# juanK.net
KiCad netlist of a schematic drawn in EAGLE
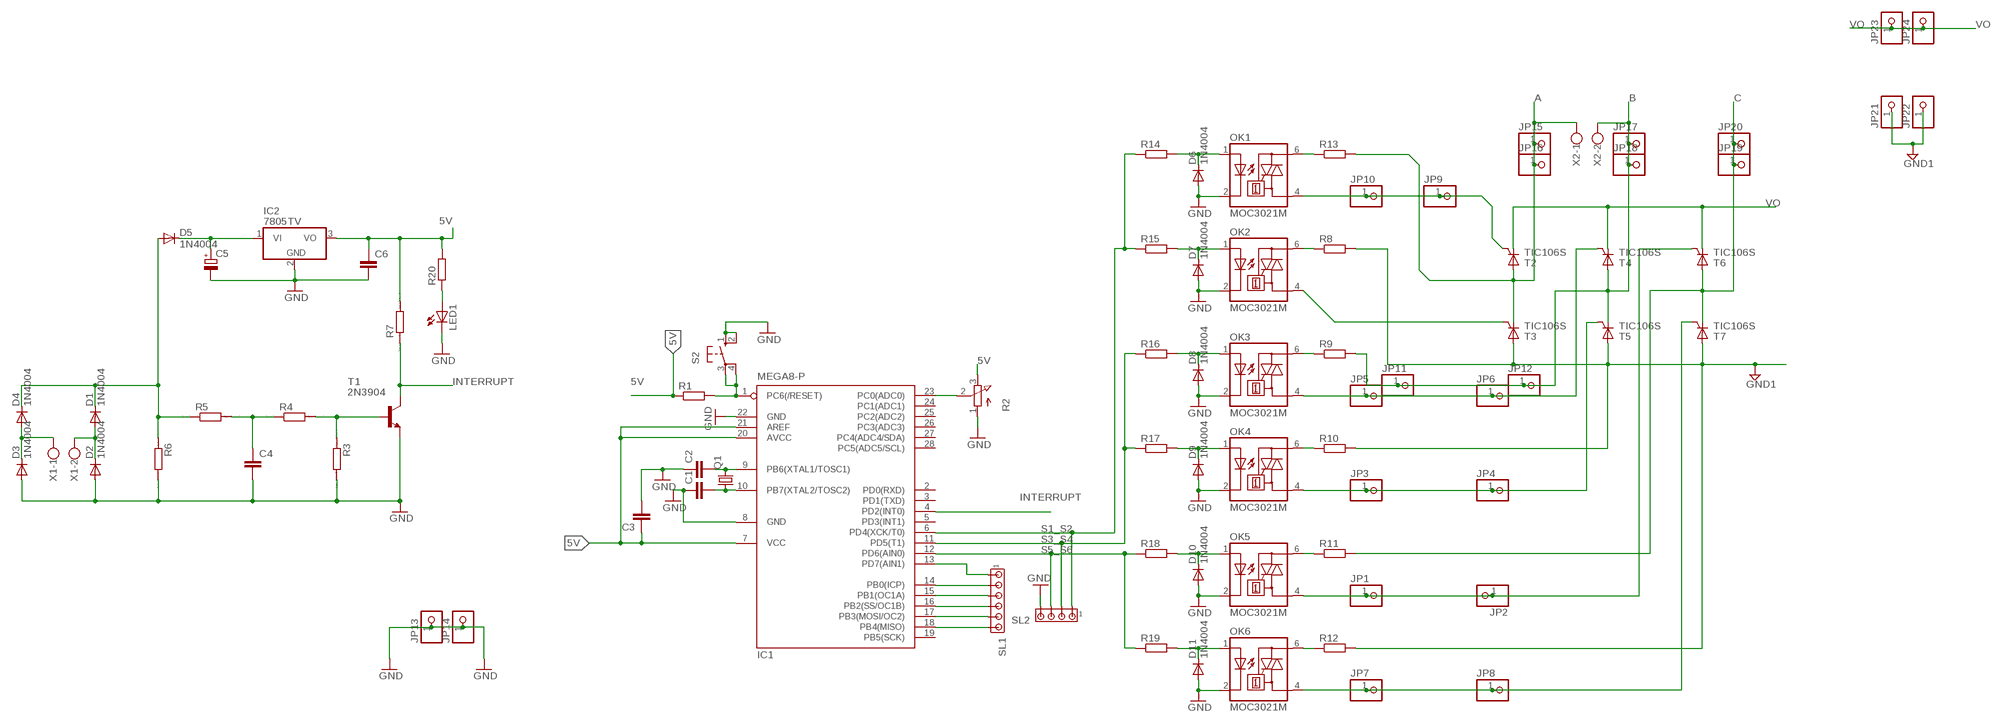
[diagram p0: schematic, sheet 1]

(export (version "E")
  (design (tool "Eeschema 10.0.6"))
  (components
    (comp (ref "C1")
      (value "C2,5-3")
      (footprint "eagle-import:C2.5-3")
      (libsource (lib "eagle-import") (part "C2,5-3"))
    )
    (comp (ref "C2")
      (value "C2,5-3")
      (footprint "eagle-import:C2.5-3")
      (libsource (lib "eagle-import") (part "C2,5-3"))
    )
    (comp (ref "C3")
      (value "C2,5-3")
      (footprint "eagle-import:C2.5-3")
      (libsource (lib "eagle-import") (part "C2,5-3"))
    )
    (comp (ref "C4")
      (value "C-EU025-025X050")
      (footprint "eagle-import:C025-025X050")
      (libsource (lib "eagle-import") (part "C-EU025-025X050"))
    )
    (comp (ref "C5")
      (value "CPOL-EUE5-10.5")
      (footprint "eagle-import:E5-10,5")
      (libsource (lib "eagle-import") (part "CPOL-EUE5-10.5"))
    )
    (comp (ref "C6")
      (value "C-EU025-025X050")
      (footprint "eagle-import:C025-025X050")
      (libsource (lib "eagle-import") (part "C-EU025-025X050"))
    )
    (comp (ref "D1")
      (value "1N4004")
      (footprint "eagle-import:DO41-10")
      (libsource (lib "eagle-import") (part "1N4004"))
    )
    (comp (ref "D2")
      (value "1N4004")
      (footprint "eagle-import:DO41-10")
      (libsource (lib "eagle-import") (part "1N4004"))
    )
    (comp (ref "D3")
      (value "1N4004")
      (footprint "eagle-import:DO41-10")
      (libsource (lib "eagle-import") (part "1N4004"))
    )
    (comp (ref "D4")
      (value "1N4004")
      (footprint "eagle-import:DO41-10")
      (libsource (lib "eagle-import") (part "1N4004"))
    )
    (comp (ref "D5")
      (value "1N4004")
      (footprint "eagle-import:DO41-10")
      (libsource (lib "eagle-import") (part "1N4004"))
    )
    (comp (ref "D6")
      (value "1N4004")
      (footprint "eagle-import:DO41-10")
      (libsource (lib "eagle-import") (part "1N4004"))
    )
    (comp (ref "D7")
      (value "1N4004")
      (footprint "eagle-import:DO41-10")
      (libsource (lib "eagle-import") (part "1N4004"))
    )
    (comp (ref "D8")
      (value "1N4004")
      (footprint "eagle-import:DO41-10")
      (libsource (lib "eagle-import") (part "1N4004"))
    )
    (comp (ref "D9")
      (value "1N4004")
      (footprint "eagle-import:DO41-10")
      (libsource (lib "eagle-import") (part "1N4004"))
    )
    (comp (ref "D10")
      (value "1N4004")
      (footprint "eagle-import:DO41-10")
      (libsource (lib "eagle-import") (part "1N4004"))
    )
    (comp (ref "D11")
      (value "1N4004")
      (footprint "eagle-import:DO41-10")
      (libsource (lib "eagle-import") (part "1N4004"))
    )
    (comp (ref "IC1")
      (value "MEGA8-P")
      (footprint "eagle-import:DIL28-3")
      (libsource (lib "eagle-import") (part "MEGA8-P"))
    )
    (comp (ref "IC2")
      (value "7805TV")
      (footprint "eagle-import:TO220V")
      (libsource (lib "eagle-import") (part "78TV05"))
    )
    (comp (ref "JP1")
      (value "PINHD-1X1")
      (footprint "eagle-import:1X01")
      (libsource (lib "eagle-import") (part "PINHD-1X1"))
    )
    (comp (ref "JP2")
      (value "PINHD-1X1")
      (footprint "eagle-import:1X01")
      (libsource (lib "eagle-import") (part "PINHD-1X1"))
    )
    (comp (ref "JP3")
      (value "PINHD-1X1")
      (footprint "eagle-import:1X01")
      (libsource (lib "eagle-import") (part "PINHD-1X1"))
    )
    (comp (ref "JP4")
      (value "PINHD-1X1")
      (footprint "eagle-import:1X01")
      (libsource (lib "eagle-import") (part "PINHD-1X1"))
    )
    (comp (ref "JP5")
      (value "PINHD-1X1")
      (footprint "eagle-import:1X01")
      (libsource (lib "eagle-import") (part "PINHD-1X1"))
    )
    (comp (ref "JP6")
      (value "PINHD-1X1")
      (footprint "eagle-import:1X01")
      (libsource (lib "eagle-import") (part "PINHD-1X1"))
    )
    (comp (ref "JP7")
      (value "PINHD-1X1")
      (footprint "eagle-import:1X01")
      (libsource (lib "eagle-import") (part "PINHD-1X1"))
    )
    (comp (ref "JP8")
      (value "PINHD-1X1")
      (footprint "eagle-import:1X01")
      (libsource (lib "eagle-import") (part "PINHD-1X1"))
    )
    (comp (ref "JP9")
      (value "PINHD-1X1")
      (footprint "eagle-import:1X01")
      (libsource (lib "eagle-import") (part "PINHD-1X1"))
    )
    (comp (ref "JP10")
      (value "PINHD-1X1")
      (footprint "eagle-import:1X01")
      (libsource (lib "eagle-import") (part "PINHD-1X1"))
    )
    (comp (ref "JP11")
      (value "PINHD-1X1")
      (footprint "eagle-import:1X01")
      (libsource (lib "eagle-import") (part "PINHD-1X1"))
    )
    (comp (ref "JP12")
      (value "PINHD-1X1")
      (footprint "eagle-import:1X01")
      (libsource (lib "eagle-import") (part "PINHD-1X1"))
    )
    (comp (ref "JP13")
      (value "PINHD-1X1")
      (footprint "eagle-import:1X01")
      (libsource (lib "eagle-import") (part "PINHD-1X1"))
    )
    (comp (ref "JP14")
      (value "PINHD-1X1")
      (footprint "eagle-import:1X01")
      (libsource (lib "eagle-import") (part "PINHD-1X1"))
    )
    (comp (ref "JP15")
      (value "PINHD-1X1")
      (footprint "eagle-import:1X01")
      (libsource (lib "eagle-import") (part "PINHD-1X1"))
    )
    (comp (ref "JP16")
      (value "PINHD-1X1")
      (footprint "eagle-import:1X01")
      (libsource (lib "eagle-import") (part "PINHD-1X1"))
    )
    (comp (ref "JP17")
      (value "PINHD-1X1")
      (footprint "eagle-import:1X01")
      (libsource (lib "eagle-import") (part "PINHD-1X1"))
    )
    (comp (ref "JP18")
      (value "PINHD-1X1")
      (footprint "eagle-import:1X01")
      (libsource (lib "eagle-import") (part "PINHD-1X1"))
    )
    (comp (ref "JP19")
      (value "PINHD-1X1")
      (footprint "eagle-import:1X01")
      (libsource (lib "eagle-import") (part "PINHD-1X1"))
    )
    (comp (ref "JP20")
      (value "PINHD-1X1")
      (footprint "eagle-import:1X01")
      (libsource (lib "eagle-import") (part "PINHD-1X1"))
    )
    (comp (ref "JP21")
      (value "PINHD-1X1")
      (footprint "eagle-import:1X01")
      (libsource (lib "eagle-import") (part "PINHD-1X1"))
    )
    (comp (ref "JP22")
      (value "PINHD-1X1")
      (footprint "eagle-import:1X01")
      (libsource (lib "eagle-import") (part "PINHD-1X1"))
    )
    (comp (ref "JP23")
      (value "PINHD-1X1")
      (footprint "eagle-import:1X01")
      (libsource (lib "eagle-import") (part "PINHD-1X1"))
    )
    (comp (ref "JP24")
      (value "PINHD-1X1")
      (footprint "eagle-import:1X01")
      (libsource (lib "eagle-import") (part "PINHD-1X1"))
    )
    (comp (ref "LED1")
      (value "LED3MM")
      (footprint "eagle-import:LED3MM")
      (libsource (lib "eagle-import") (part "LED3MM"))
    )
    (comp (ref "OK1")
      (value "MOC3021M")
      (footprint "eagle-import:DIL06")
      (fields (field (name "MF") "FAIRCHILD SEMICONDUCTOR") (field (name "MPN") "MOC3021-M"))
      (libsource (lib "eagle-import") (part "MOC30M21"))
    )
    (comp (ref "OK2")
      (value "MOC3021M")
      (footprint "eagle-import:DIL06")
      (fields (field (name "MF") "FAIRCHILD SEMICONDUCTOR") (field (name "MPN") "MOC3021-M"))
      (libsource (lib "eagle-import") (part "MOC30M21"))
    )
    (comp (ref "OK3")
      (value "MOC3021M")
      (footprint "eagle-import:DIL06")
      (fields (field (name "MF") "FAIRCHILD SEMICONDUCTOR") (field (name "MPN") "MOC3021-M"))
      (libsource (lib "eagle-import") (part "MOC30M21"))
    )
    (comp (ref "OK4")
      (value "MOC3021M")
      (footprint "eagle-import:DIL06")
      (fields (field (name "MF") "FAIRCHILD SEMICONDUCTOR") (field (name "MPN") "MOC3021-M"))
      (libsource (lib "eagle-import") (part "MOC30M21"))
    )
    (comp (ref "OK5")
      (value "MOC3021M")
      (footprint "eagle-import:DIL06")
      (fields (field (name "MF") "FAIRCHILD SEMICONDUCTOR") (field (name "MPN") "MOC3021-M"))
      (libsource (lib "eagle-import") (part "MOC30M21"))
    )
    (comp (ref "OK6")
      (value "MOC3021M")
      (footprint "eagle-import:DIL06")
      (fields (field (name "MF") "FAIRCHILD SEMICONDUCTOR") (field (name "MPN") "MOC3021-M"))
      (libsource (lib "eagle-import") (part "MOC30M21"))
    )
    (comp (ref "Q1")
      (value "CRYSTALHC49U70")
      (footprint "eagle-import:HC49U70")
      (libsource (lib "eagle-import") (part "CRYSTALHC49U70"))
    )
    (comp (ref "R1")
      (value "R-EU_0204/5")
      (footprint "eagle-import:0204_5")
      (libsource (lib "eagle-import") (part "R-EU_0204/5"))
    )
    (comp (ref "R2")
      (value "3RP/1610N")
      (footprint "eagle-import:3RP_1610N")
      (libsource (lib "eagle-import") (part "3RP/1610N"))
    )
    (comp (ref "R3")
      (value "R0204/7")
      (footprint "eagle-import:0204_7")
      (libsource (lib "eagle-import") (part "R0204/7"))
    )
    (comp (ref "R4")
      (value "R0204/7")
      (footprint "eagle-import:0204_7")
      (libsource (lib "eagle-import") (part "R0204/7"))
    )
    (comp (ref "R5")
      (value "R0204/7")
      (footprint "eagle-import:0204_7")
      (libsource (lib "eagle-import") (part "R0204/7"))
    )
    (comp (ref "R6")
      (value "R0204/7")
      (footprint "eagle-import:0204_7")
      (libsource (lib "eagle-import") (part "R0204/7"))
    )
    (comp (ref "R7")
      (value "R0204/7")
      (footprint "eagle-import:0204_7")
      (libsource (lib "eagle-import") (part "R0204/7"))
    )
    (comp (ref "R8")
      (value "R-EU_0817/22")
      (footprint "eagle-import:P0817_22")
      (libsource (lib "eagle-import") (part "resistor_R-EU_0817/22"))
    )
    (comp (ref "R9")
      (value "R-EU_0817/22")
      (footprint "eagle-import:P0817_22")
      (libsource (lib "eagle-import") (part "resistor_R-EU_0817/22"))
    )
    (comp (ref "R10")
      (value "R-EU_0817/22")
      (footprint "eagle-import:P0817_22")
      (libsource (lib "eagle-import") (part "resistor_R-EU_0817/22"))
    )
    (comp (ref "R11")
      (value "R-EU_0817/22")
      (footprint "eagle-import:P0817_22")
      (libsource (lib "eagle-import") (part "resistor_R-EU_0817/22"))
    )
    (comp (ref "R12")
      (value "R-EU_0817/22")
      (footprint "eagle-import:P0817_22")
      (libsource (lib "eagle-import") (part "resistor_R-EU_0817/22"))
    )
    (comp (ref "R13")
      (value "R-EU_0817/22")
      (footprint "eagle-import:P0817_22")
      (libsource (lib "eagle-import") (part "resistor_R-EU_0817/22"))
    )
    (comp (ref "R14")
      (value "R-EU_0204/7")
      (footprint "eagle-import:0204_7")
      (libsource (lib "eagle-import") (part "resistor_R-EU_0204/7"))
    )
    (comp (ref "R15")
      (value "R-EU_0204/7")
      (footprint "eagle-import:0204_7")
      (libsource (lib "eagle-import") (part "resistor_R-EU_0204/7"))
    )
    (comp (ref "R16")
      (value "R-EU_0204/7")
      (footprint "eagle-import:0204_7")
      (libsource (lib "eagle-import") (part "resistor_R-EU_0204/7"))
    )
    (comp (ref "R17")
      (value "R-EU_0204/7")
      (footprint "eagle-import:0204_7")
      (libsource (lib "eagle-import") (part "resistor_R-EU_0204/7"))
    )
    (comp (ref "R18")
      (value "R-EU_0204/7")
      (footprint "eagle-import:0204_7")
      (libsource (lib "eagle-import") (part "resistor_R-EU_0204/7"))
    )
    (comp (ref "R19")
      (value "R-EU_0204/7")
      (footprint "eagle-import:0204_7")
      (libsource (lib "eagle-import") (part "resistor_R-EU_0204/7"))
    )
    (comp (ref "R20")
      (value "R-EU_0204/5")
      (footprint "eagle-import:0204_5")
      (libsource (lib "eagle-import") (part "R-EU_0204/5"))
    )
    (comp (ref "S2")
      (value "10-XX")
      (footprint "eagle-import:B3F-10XX")
      (fields (field (name "MPN") "B3F-1000"))
      (libsource (lib "eagle-import") (part "10-XX"))
    )
    (comp (ref "SL1")
      (value "MTA06-100")
      (footprint "eagle-import:10X06MTA")
      (libsource (lib "eagle-import") (part "MTA06-100"))
    )
    (comp (ref "SL2")
      (value "MTA04-100")
      (footprint "eagle-import:10X04MTA")
      (libsource (lib "eagle-import") (part "MTA04-100"))
    )
    (comp (ref "T1")
      (value "2N3904")
      (footprint "eagle-import:TO92")
      (libsource (lib "eagle-import") (part "2N3904"))
    )
    (comp (ref "T2")
      (value "TIC106S")
      (footprint "eagle-import:TIC106S")
      (libsource (lib "eagle-import") (part "TIC106S"))
    )
    (comp (ref "T3")
      (value "TIC106S")
      (footprint "eagle-import:TIC106S")
      (libsource (lib "eagle-import") (part "TIC106S"))
    )
    (comp (ref "T4")
      (value "TIC106S")
      (footprint "eagle-import:TIC106S")
      (libsource (lib "eagle-import") (part "TIC106S"))
    )
    (comp (ref "T5")
      (value "TIC106S")
      (footprint "eagle-import:TIC106S")
      (libsource (lib "eagle-import") (part "TIC106S"))
    )
    (comp (ref "T6")
      (value "TIC106S")
      (footprint "eagle-import:TIC106S")
      (libsource (lib "eagle-import") (part "TIC106S"))
    )
    (comp (ref "T7")
      (value "TIC106S")
      (footprint "eagle-import:TIC106S")
      (libsource (lib "eagle-import") (part "TIC106S"))
    )
    (comp (ref "X1")
      (value "W237-102")
      (footprint "eagle-import:W237-102")
      (fields (field (name "MPN") "237-102"))
      (libsource (lib "eagle-import") (part "W237-102"))
    )
    (comp (ref "X2")
      (value "W237-102")
      (footprint "eagle-import:W237-102")
      (fields (field (name "MPN") "237-102"))
      (libsource (lib "eagle-import") (part "W237-102"))
    )
  )
  (nets
    (net (code "1") (name "/A") (class "Default")
      (node (ref "JP15") (pin "1") (pinfunction "1_1") (pintype "passive"))
      (node (ref "JP16") (pin "1") (pinfunction "1_1") (pintype "passive"))
      (node (ref "R13") (pin "2") (pinfunction "2_2") (pintype "passive"))
      (node (ref "T2") (pin "A") (pinfunction "A_A") (pintype "passive"))
      (node (ref "T3") (pin "C") (pinfunction "C_C") (pintype "passive"))
      (node (ref "X2") (pin "1") (pinfunction "KL_1") (pintype "passive"))
    )
    (net (code "2") (name "/B") (class "Default")
      (node (ref "JP11") (pin "1") (pinfunction "1_1") (pintype "passive"))
      (node (ref "JP12") (pin "1") (pinfunction "1_1") (pintype "passive"))
      (node (ref "JP17") (pin "1") (pinfunction "1_1") (pintype "passive"))
      (node (ref "JP18") (pin "1") (pinfunction "1_1") (pintype "passive"))
      (node (ref "R9") (pin "2") (pinfunction "2_2") (pintype "passive"))
      (node (ref "T4") (pin "A") (pinfunction "A_A") (pintype "passive"))
      (node (ref "T5") (pin "C") (pinfunction "C_C") (pintype "passive"))
      (node (ref "X2") (pin "2") (pinfunction "KL_2") (pintype "passive"))
    )
    (net (code "3") (name "/C") (class "Default")
      (node (ref "JP19") (pin "1") (pinfunction "1_1") (pintype "passive"))
      (node (ref "JP20") (pin "1") (pinfunction "1_1") (pintype "passive"))
      (node (ref "R11") (pin "2") (pinfunction "2_2") (pintype "passive"))
      (node (ref "T6") (pin "A") (pinfunction "A_A") (pintype "passive"))
      (node (ref "T7") (pin "C") (pinfunction "C_C") (pintype "passive"))
    )
    (net (code "4") (name "/INTERRUPT") (class "Default")
      (node (ref "IC1") (pin "4") (pinfunction "PD2(INT0)_4") (pintype "bidirectional"))
      (node (ref "R7") (pin "1") (pinfunction "1_1") (pintype "passive"))
      (node (ref "T1") (pin "1") (pinfunction "C_1") (pintype "passive"))
    )
    (net (code "5") (name "/S1_S2") (class "Default")
      (node (ref "IC1") (pin "6") (pinfunction "PD4(XCK/T0)_6") (pintype "bidirectional"))
      (node (ref "R14") (pin "1") (pinfunction "1_1") (pintype "passive"))
      (node (ref "R15") (pin "1") (pinfunction "1_1") (pintype "passive"))
      (node (ref "SL2") (pin "1") (pinfunction "1_1") (pintype "passive"))
    )
    (net (code "6") (name "/S3_S4") (class "Default")
      (node (ref "IC1") (pin "11") (pinfunction "PD5(T1)_11") (pintype "bidirectional"))
      (node (ref "R16") (pin "1") (pinfunction "1_1") (pintype "passive"))
      (node (ref "R17") (pin "1") (pinfunction "1_1") (pintype "passive"))
      (node (ref "SL2") (pin "2") (pinfunction "2_2") (pintype "passive"))
    )
    (net (code "7") (name "/S5_S6") (class "Default")
      (node (ref "IC1") (pin "12") (pinfunction "PD6(AIN0)_12") (pintype "bidirectional"))
      (node (ref "R18") (pin "1") (pinfunction "1_1") (pintype "passive"))
      (node (ref "R19") (pin "1") (pinfunction "1_1") (pintype "passive"))
      (node (ref "SL2") (pin "3") (pinfunction "3_3") (pintype "passive"))
    )
    (net (code "8") (name "/VO") (class "Default")
      (node (ref "JP23") (pin "1") (pinfunction "1_1") (pintype "passive"))
      (node (ref "JP24") (pin "1") (pinfunction "1_1") (pintype "passive"))
      (node (ref "T2") (pin "C") (pinfunction "C_C") (pintype "passive"))
      (node (ref "T4") (pin "C") (pinfunction "C_C") (pintype "passive"))
      (node (ref "T6") (pin "C") (pinfunction "C_C") (pintype "passive"))
    )
    (net (code "9") (name "5V") (class "Default")
      (node (ref "C3") (pin "1") (pinfunction "1_1") (pintype "passive"))
      (node (ref "C6") (pin "1") (pinfunction "1_1") (pintype "passive"))
      (node (ref "IC1") (pin "20") (pinfunction "AVCC_20") (pintype "power_in"))
      (node (ref "IC1") (pin "21") (pinfunction "AREF_21") (pintype "passive"))
      (node (ref "IC1") (pin "7") (pinfunction "VCC_7") (pintype "power_in"))
      (node (ref "IC2") (pin "3") (pinfunction "VO_3") (pintype "passive"))
      (node (ref "R1") (pin "1") (pinfunction "1_1") (pintype "passive"))
      (node (ref "R2") (pin "3") (pinfunction "E_3") (pintype "passive"))
      (node (ref "R20") (pin "2") (pinfunction "2_2") (pintype "passive"))
      (node (ref "R7") (pin "2") (pinfunction "2_2") (pintype "passive"))
    )
    (net (code "10") (name "GND") (class "Default")
      (node (ref "C1") (pin "1") (pinfunction "1_1") (pintype "passive"))
      (node (ref "C2") (pin "1") (pinfunction "1_1") (pintype "passive"))
      (node (ref "C3") (pin "2") (pinfunction "2_2") (pintype "passive"))
      (node (ref "C4") (pin "2") (pinfunction "2_2") (pintype "passive"))
      (node (ref "C5") (pin "-") (pinfunction "-_-") (pintype "passive"))
      (node (ref "C6") (pin "2") (pinfunction "2_2") (pintype "passive"))
      (node (ref "D10") (pin "A") (pinfunction "A_A") (pintype "passive"))
      (node (ref "D11") (pin "A") (pinfunction "A_A") (pintype "passive"))
      (node (ref "D2") (pin "A") (pinfunction "A_A") (pintype "passive"))
      (node (ref "D3") (pin "A") (pinfunction "A_A") (pintype "passive"))
      (node (ref "D6") (pin "A") (pinfunction "A_A") (pintype "passive"))
      (node (ref "D7") (pin "A") (pinfunction "A_A") (pintype "passive"))
      (node (ref "D8") (pin "A") (pinfunction "A_A") (pintype "passive"))
      (node (ref "D9") (pin "A") (pinfunction "A_A") (pintype "passive"))
      (node (ref "IC1") (pin "22") (pinfunction "GND_22") (pintype "power_in"))
      (node (ref "IC1") (pin "8") (pinfunction "GND_8") (pintype "power_in"))
      (node (ref "IC2") (pin "2") (pinfunction "GND_2") (pintype "passive"))
      (node (ref "JP13") (pin "1") (pinfunction "1_1") (pintype "passive"))
      (node (ref "JP14") (pin "1") (pinfunction "1_1") (pintype "passive"))
      (node (ref "LED1") (pin "K") (pinfunction "C_K") (pintype "passive"))
      (node (ref "OK1") (pin "2") (pinfunction "C_2") (pintype "passive"))
      (node (ref "OK2") (pin "2") (pinfunction "C_2") (pintype "passive"))
      (node (ref "OK3") (pin "2") (pinfunction "C_2") (pintype "passive"))
      (node (ref "OK4") (pin "2") (pinfunction "C_2") (pintype "passive"))
      (node (ref "OK5") (pin "2") (pinfunction "C_2") (pintype "passive"))
      (node (ref "OK6") (pin "2") (pinfunction "C_2") (pintype "passive"))
      (node (ref "R2") (pin "1") (pinfunction "A_1") (pintype "passive"))
      (node (ref "R3") (pin "2") (pinfunction "2_2") (pintype "passive"))
      (node (ref "R6") (pin "2") (pinfunction "2_2") (pintype "passive"))
      (node (ref "S2") (pin "1") (pinfunction "S_1") (pintype "passive"))
      (node (ref "S2") (pin "2") (pinfunction "S1_2") (pintype "passive"))
      (node (ref "SL2") (pin "4") (pinfunction "4_4") (pintype "passive"))
      (node (ref "T1") (pin "3") (pinfunction "E_3") (pintype "passive"))
    )
    (net (code "11") (name "GND1") (class "Default")
      (node (ref "JP21") (pin "1") (pinfunction "1_1") (pintype "passive"))
      (node (ref "JP22") (pin "1") (pinfunction "1_1") (pintype "passive"))
      (node (ref "R10") (pin "2") (pinfunction "2_2") (pintype "passive"))
      (node (ref "R12") (pin "2") (pinfunction "2_2") (pintype "passive"))
      (node (ref "R8") (pin "2") (pinfunction "2_2") (pintype "passive"))
      (node (ref "T3") (pin "A") (pinfunction "A_A") (pintype "passive"))
      (node (ref "T5") (pin "A") (pinfunction "A_A") (pintype "passive"))
      (node (ref "T7") (pin "A") (pinfunction "A_A") (pintype "passive"))
    )
    (net (code "12") (name "Net-(C4-Pad1)") (class "Default")
      (node (ref "C4") (pin "1") (pinfunction "1_1") (pintype "passive"))
      (node (ref "R4") (pin "1") (pinfunction "1_1") (pintype "passive"))
      (node (ref "R5") (pin "2") (pinfunction "2_2") (pintype "passive"))
    )
    (net (code "13") (name "Net-(D1-PadC)") (class "Default")
      (node (ref "D1") (pin "C") (pinfunction "C_C") (pintype "passive"))
      (node (ref "D4") (pin "C") (pinfunction "C_C") (pintype "passive"))
      (node (ref "D5") (pin "A") (pinfunction "A_A") (pintype "passive"))
      (node (ref "R5") (pin "1") (pinfunction "1_1") (pintype "passive"))
      (node (ref "R6") (pin "1") (pinfunction "1_1") (pintype "passive"))
    )
    (net (code "14") (name "Net-(IC1-PB0(ICP))") (class "Default")
      (node (ref "IC1") (pin "14") (pinfunction "PB0(ICP)_14") (pintype "bidirectional"))
      (node (ref "SL1") (pin "2") (pinfunction "2_2") (pintype "passive"))
    )
    (net (code "15") (name "Net-(IC1-PB1(OC1A))") (class "Default")
      (node (ref "IC1") (pin "15") (pinfunction "PB1(OC1A)_15") (pintype "bidirectional"))
      (node (ref "SL1") (pin "3") (pinfunction "3_3") (pintype "passive"))
    )
    (net (code "16") (name "Net-(IC1-PB2(SS{slash}OC1B))") (class "Default")
      (node (ref "IC1") (pin "16") (pinfunction "PB2(SS/OC1B)_16") (pintype "bidirectional"))
      (node (ref "SL1") (pin "4") (pinfunction "4_4") (pintype "passive"))
    )
    (net (code "17") (name "Net-(IC1-PB3(MOSI{slash}OC2))") (class "Default")
      (node (ref "IC1") (pin "17") (pinfunction "PB3(MOSI/OC2)_17") (pintype "bidirectional"))
      (node (ref "SL1") (pin "5") (pinfunction "5_5") (pintype "passive"))
    )
    (net (code "18") (name "Net-(IC1-PB4(MISO))") (class "Default")
      (node (ref "IC1") (pin "18") (pinfunction "PB4(MISO)_18") (pintype "bidirectional"))
      (node (ref "SL1") (pin "6") (pinfunction "6_6") (pintype "passive"))
    )
    (net (code "19") (name "Net-(IC1-PB6(XTAL1{slash}TOSC1))") (class "Default")
      (node (ref "C2") (pin "2") (pinfunction "2_2") (pintype "passive"))
      (node (ref "IC1") (pin "9") (pinfunction "PB6(XTAL1/TOSC1)_9") (pintype "bidirectional"))
      (node (ref "Q1") (pin "2") (pinfunction "2_2") (pintype "passive"))
    )
    (net (code "20") (name "Net-(IC1-PB7(XTAL2{slash}TOSC2))") (class "Default")
      (node (ref "C1") (pin "2") (pinfunction "2_2") (pintype "passive"))
      (node (ref "IC1") (pin "10") (pinfunction "PB7(XTAL2/TOSC2)_10") (pintype "bidirectional"))
      (node (ref "Q1") (pin "1") (pinfunction "1_1") (pintype "passive"))
    )
    (net (code "21") (name "Net-(IC1-PC0(ADC0))") (class "Default")
      (node (ref "IC1") (pin "23") (pinfunction "PC0(ADC0)_23") (pintype "bidirectional"))
      (node (ref "R2") (pin "2") (pinfunction "S_2") (pintype "passive"))
    )
    (net (code "22") (name "Net-(IC1-PC6({slash}RESET))") (class "Default")
      (node (ref "IC1") (pin "1") (pinfunction "PC6(/RESET)_1") (pintype "bidirectional"))
      (node (ref "R1") (pin "2") (pinfunction "2_2") (pintype "passive"))
      (node (ref "S2") (pin "3") (pinfunction "P_3") (pintype "passive"))
      (node (ref "S2") (pin "4") (pinfunction "P1_4") (pintype "passive"))
    )
    (net (code "23") (name "Net-(IC1-PD7(AIN1))") (class "Default")
      (node (ref "IC1") (pin "13") (pinfunction "PD7(AIN1)_13") (pintype "bidirectional"))
      (node (ref "SL1") (pin "1") (pinfunction "1_1") (pintype "passive"))
    )
    (net (code "24") (name "Net-(IC2-VI)") (class "Default")
      (node (ref "C5") (pin "+") (pinfunction "+_+") (pintype "passive"))
      (node (ref "D5") (pin "C") (pinfunction "C_C") (pintype "passive"))
      (node (ref "IC2") (pin "1") (pinfunction "VI_1") (pintype "input"))
    )
    (net (code "25") (name "Net-(LED1-PadA)") (class "Default")
      (node (ref "LED1") (pin "A") (pinfunction "A_A") (pintype "passive"))
      (node (ref "R20") (pin "1") (pinfunction "1_1") (pintype "passive"))
    )
    (net (code "26") (name "Net-(OK1-A)") (class "Default")
      (node (ref "D6") (pin "C") (pinfunction "C_C") (pintype "passive"))
      (node (ref "OK1") (pin "1") (pinfunction "A_1") (pintype "passive"))
      (node (ref "R14") (pin "2") (pinfunction "2_2") (pintype "passive"))
    )
    (net (code "27") (name "Net-(OK1-A1)") (class "Default")
      (node (ref "JP10") (pin "1") (pinfunction "1_1") (pintype "passive"))
      (node (ref "JP9") (pin "1") (pinfunction "1_1") (pintype "passive"))
      (node (ref "OK1") (pin "4") (pinfunction "A1_4") (pintype "passive"))
      (node (ref "T2") (pin "G") (pinfunction "G_G") (pintype "passive"))
    )
    (net (code "28") (name "Net-(OK1-A2)") (class "Default")
      (node (ref "OK1") (pin "6") (pinfunction "A2_6") (pintype "passive"))
      (node (ref "R13") (pin "1") (pinfunction "1_1") (pintype "passive"))
    )
    (net (code "29") (name "Net-(OK2-A)") (class "Default")
      (node (ref "D7") (pin "C") (pinfunction "C_C") (pintype "passive"))
      (node (ref "OK2") (pin "1") (pinfunction "A_1") (pintype "passive"))
      (node (ref "R15") (pin "2") (pinfunction "2_2") (pintype "passive"))
    )
    (net (code "30") (name "Net-(OK2-A1)") (class "Default")
      (node (ref "OK2") (pin "4") (pinfunction "A1_4") (pintype "passive"))
      (node (ref "T3") (pin "G") (pinfunction "G_G") (pintype "passive"))
    )
    (net (code "31") (name "Net-(OK2-A2)") (class "Default")
      (node (ref "OK2") (pin "6") (pinfunction "A2_6") (pintype "passive"))
      (node (ref "R8") (pin "1") (pinfunction "1_1") (pintype "passive"))
    )
    (net (code "32") (name "Net-(OK3-A)") (class "Default")
      (node (ref "D8") (pin "C") (pinfunction "C_C") (pintype "passive"))
      (node (ref "OK3") (pin "1") (pinfunction "A_1") (pintype "passive"))
      (node (ref "R16") (pin "2") (pinfunction "2_2") (pintype "passive"))
    )
    (net (code "33") (name "Net-(OK3-A1)") (class "Default")
      (node (ref "JP5") (pin "1") (pinfunction "1_1") (pintype "passive"))
      (node (ref "JP6") (pin "1") (pinfunction "1_1") (pintype "passive"))
      (node (ref "OK3") (pin "4") (pinfunction "A1_4") (pintype "passive"))
      (node (ref "T4") (pin "G") (pinfunction "G_G") (pintype "passive"))
    )
    (net (code "34") (name "Net-(OK3-A2)") (class "Default")
      (node (ref "OK3") (pin "6") (pinfunction "A2_6") (pintype "passive"))
      (node (ref "R9") (pin "1") (pinfunction "1_1") (pintype "passive"))
    )
    (net (code "35") (name "Net-(OK4-A)") (class "Default")
      (node (ref "D9") (pin "C") (pinfunction "C_C") (pintype "passive"))
      (node (ref "OK4") (pin "1") (pinfunction "A_1") (pintype "passive"))
      (node (ref "R17") (pin "2") (pinfunction "2_2") (pintype "passive"))
    )
    (net (code "36") (name "Net-(OK4-A1)") (class "Default")
      (node (ref "JP3") (pin "1") (pinfunction "1_1") (pintype "passive"))
      (node (ref "JP4") (pin "1") (pinfunction "1_1") (pintype "passive"))
      (node (ref "OK4") (pin "4") (pinfunction "A1_4") (pintype "passive"))
      (node (ref "T5") (pin "G") (pinfunction "G_G") (pintype "passive"))
    )
    (net (code "37") (name "Net-(OK4-A2)") (class "Default")
      (node (ref "OK4") (pin "6") (pinfunction "A2_6") (pintype "passive"))
      (node (ref "R10") (pin "1") (pinfunction "1_1") (pintype "passive"))
    )
    (net (code "38") (name "Net-(OK5-A)") (class "Default")
      (node (ref "D10") (pin "C") (pinfunction "C_C") (pintype "passive"))
      (node (ref "OK5") (pin "1") (pinfunction "A_1") (pintype "passive"))
      (node (ref "R18") (pin "2") (pinfunction "2_2") (pintype "passive"))
    )
    (net (code "39") (name "Net-(OK5-A1)") (class "Default")
      (node (ref "JP1") (pin "1") (pinfunction "1_1") (pintype "passive"))
      (node (ref "JP2") (pin "1") (pinfunction "1_1") (pintype "passive"))
      (node (ref "OK5") (pin "4") (pinfunction "A1_4") (pintype "passive"))
      (node (ref "T6") (pin "G") (pinfunction "G_G") (pintype "passive"))
    )
    (net (code "40") (name "Net-(OK5-A2)") (class "Default")
      (node (ref "OK5") (pin "6") (pinfunction "A2_6") (pintype "passive"))
      (node (ref "R11") (pin "1") (pinfunction "1_1") (pintype "passive"))
    )
    (net (code "41") (name "Net-(OK6-A)") (class "Default")
      (node (ref "D11") (pin "C") (pinfunction "C_C") (pintype "passive"))
      (node (ref "OK6") (pin "1") (pinfunction "A_1") (pintype "passive"))
      (node (ref "R19") (pin "2") (pinfunction "2_2") (pintype "passive"))
    )
    (net (code "42") (name "Net-(OK6-A1)") (class "Default")
      (node (ref "JP7") (pin "1") (pinfunction "1_1") (pintype "passive"))
      (node (ref "JP8") (pin "1") (pinfunction "1_1") (pintype "passive"))
      (node (ref "OK6") (pin "4") (pinfunction "A1_4") (pintype "passive"))
      (node (ref "T7") (pin "G") (pinfunction "G_G") (pintype "passive"))
    )
    (net (code "43") (name "Net-(OK6-A2)") (class "Default")
      (node (ref "OK6") (pin "6") (pinfunction "A2_6") (pintype "passive"))
      (node (ref "R12") (pin "1") (pinfunction "1_1") (pintype "passive"))
    )
    (net (code "44") (name "Net-(T1-B)") (class "Default")
      (node (ref "R3") (pin "1") (pinfunction "1_1") (pintype "passive"))
      (node (ref "R4") (pin "2") (pinfunction "2_2") (pintype "passive"))
      (node (ref "T1") (pin "2") (pinfunction "B_2") (pintype "passive"))
    )
    (net (code "45") (name "Net-(X1A-KL)") (class "Default")
      (node (ref "D3") (pin "C") (pinfunction "C_C") (pintype "passive"))
      (node (ref "D4") (pin "A") (pinfunction "A_A") (pintype "passive"))
      (node (ref "X1") (pin "1") (pinfunction "KL_1") (pintype "passive"))
    )
    (net (code "46") (name "Net-(X1B-KL)") (class "Default")
      (node (ref "D1") (pin "A") (pinfunction "A_A") (pintype "passive"))
      (node (ref "D2") (pin "C") (pinfunction "C_C") (pintype "passive"))
      (node (ref "X1") (pin "2") (pinfunction "KL_2") (pintype "passive"))
    )
    (net (code "47") (name "unconnected-(IC1-PB5(SCK)-Pad19)") (class "Default")
      (node (ref "IC1") (pin "19") (pinfunction "PB5(SCK)_19") (pintype "bidirectional"))
    )
    (net (code "48") (name "unconnected-(IC1-PC1(ADC1)-Pad24)") (class "Default")
      (node (ref "IC1") (pin "24") (pinfunction "PC1(ADC1)_24") (pintype "bidirectional"))
    )
    (net (code "49") (name "unconnected-(IC1-PC2(ADC2)-Pad25)") (class "Default")
      (node (ref "IC1") (pin "25") (pinfunction "PC2(ADC2)_25") (pintype "bidirectional"))
    )
    (net (code "50") (name "unconnected-(IC1-PC3(ADC3)-Pad26)") (class "Default")
      (node (ref "IC1") (pin "26") (pinfunction "PC3(ADC3)_26") (pintype "bidirectional"))
    )
    (net (code "51") (name "unconnected-(IC1-PC4(ADC4{slash}SDA)-Pad27)") (class "Default")
      (node (ref "IC1") (pin "27") (pinfunction "PC4(ADC4/SDA)_27") (pintype "bidirectional"))
    )
    (net (code "52") (name "unconnected-(IC1-PC5(ADC5{slash}SCL)-Pad28)") (class "Default")
      (node (ref "IC1") (pin "28") (pinfunction "PC5(ADC5/SCL)_28") (pintype "bidirectional"))
    )
    (net (code "53") (name "unconnected-(IC1-PD0(RXD)-Pad2)") (class "Default")
      (node (ref "IC1") (pin "2") (pinfunction "PD0(RXD)_2") (pintype "bidirectional"))
    )
    (net (code "54") (name "unconnected-(IC1-PD1(TXD)-Pad3)") (class "Default")
      (node (ref "IC1") (pin "3") (pinfunction "PD1(TXD)_3") (pintype "bidirectional"))
    )
    (net (code "55") (name "unconnected-(IC1-PD3(INT1)-Pad5)") (class "Default")
      (node (ref "IC1") (pin "5") (pinfunction "PD3(INT1)_5") (pintype "bidirectional"))
    )
  )
)
